# design.net
KiCad netlist of a schematic drawn in Altium Designer
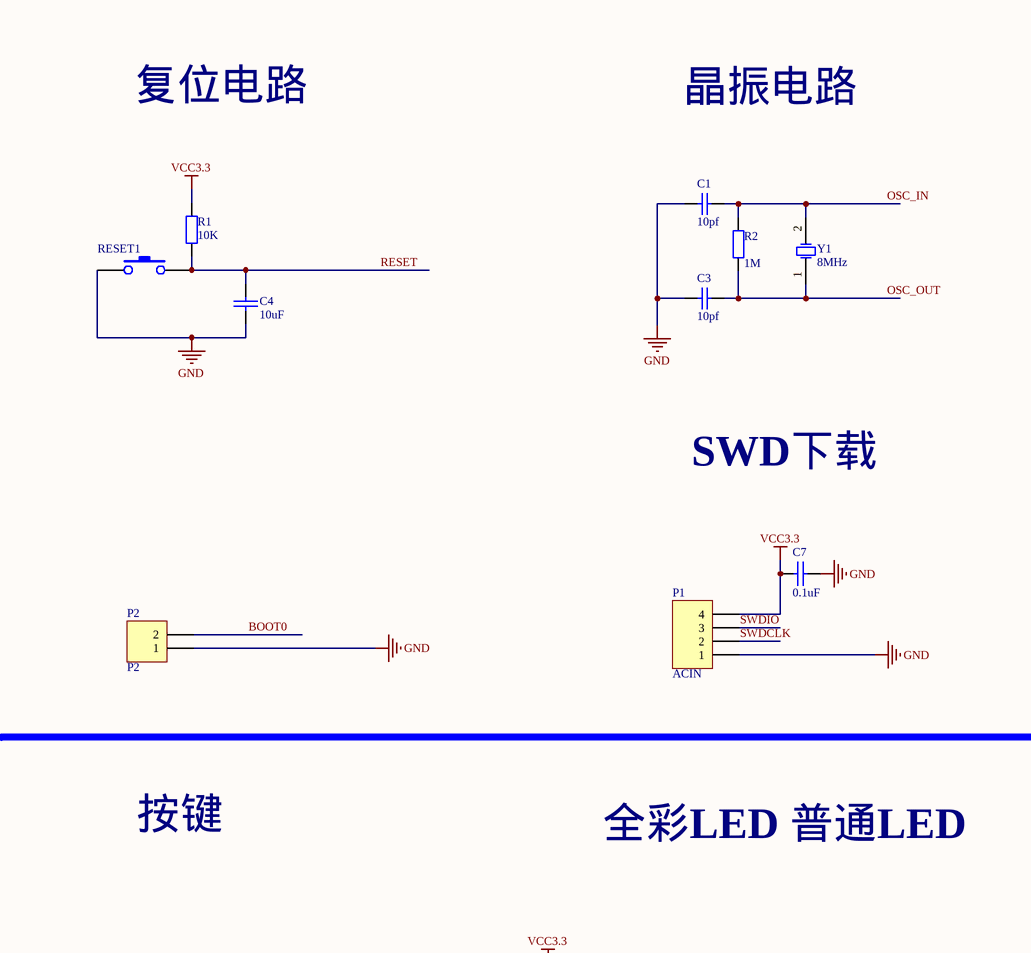
[diagram p0: 温湿度.SchDoc, top left]
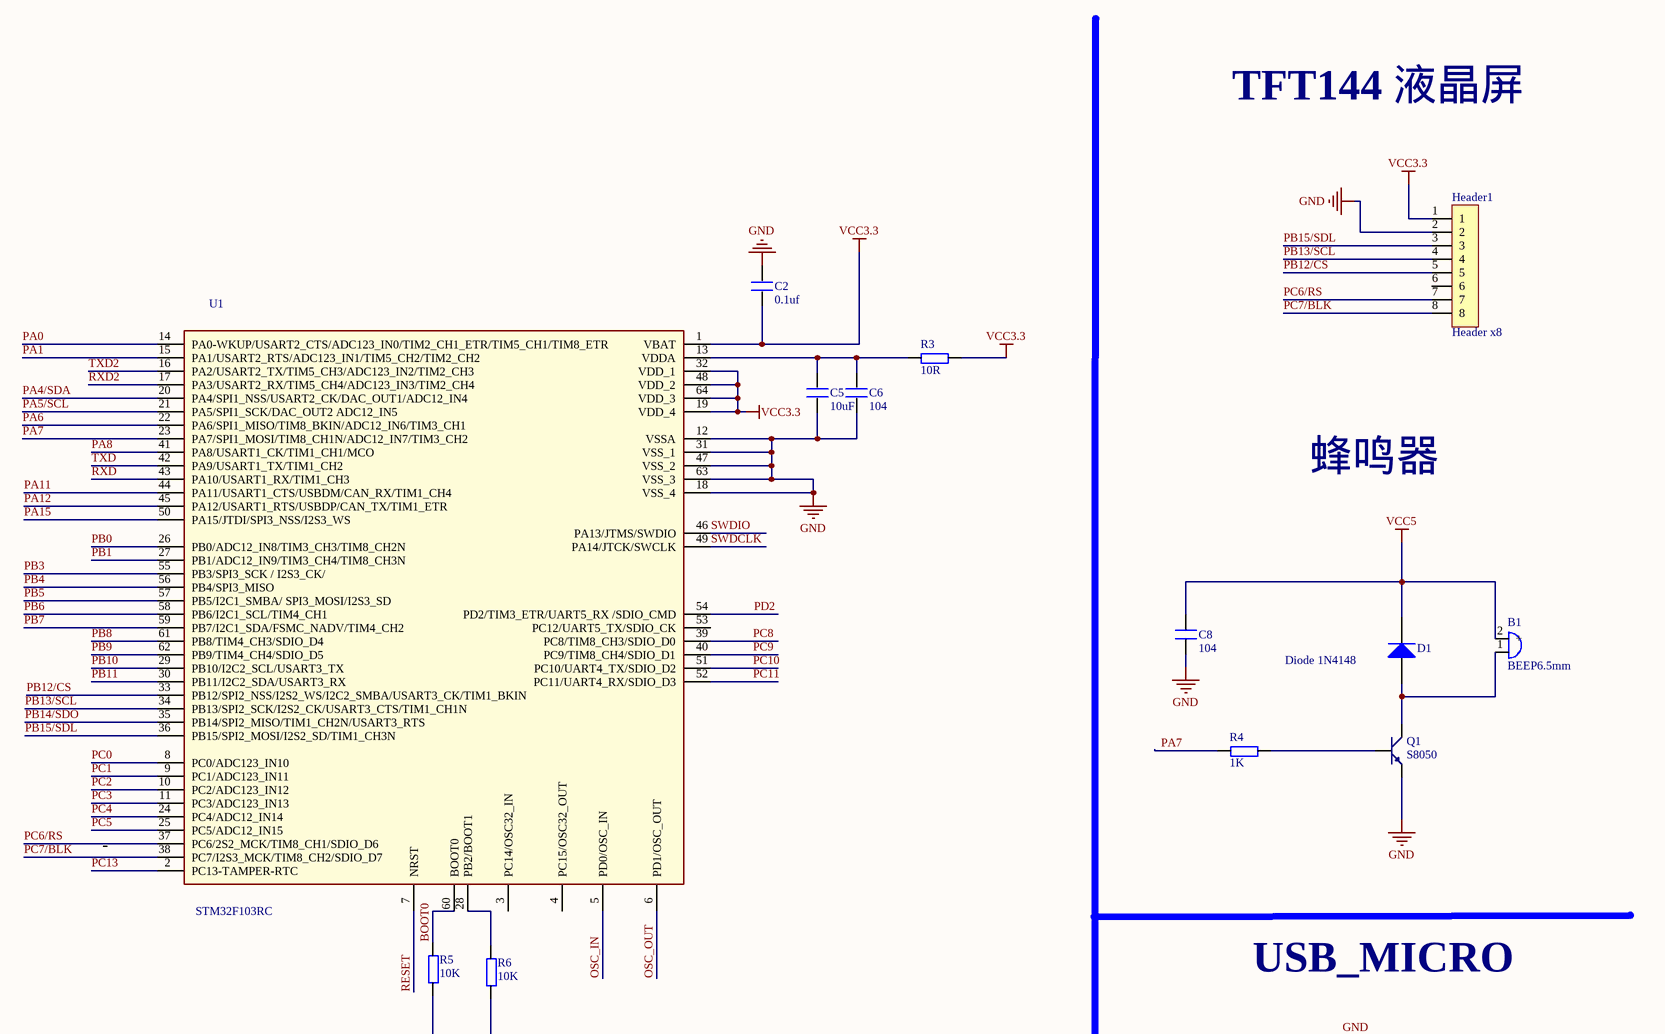
[diagram p1: 温湿度.SchDoc, top right]
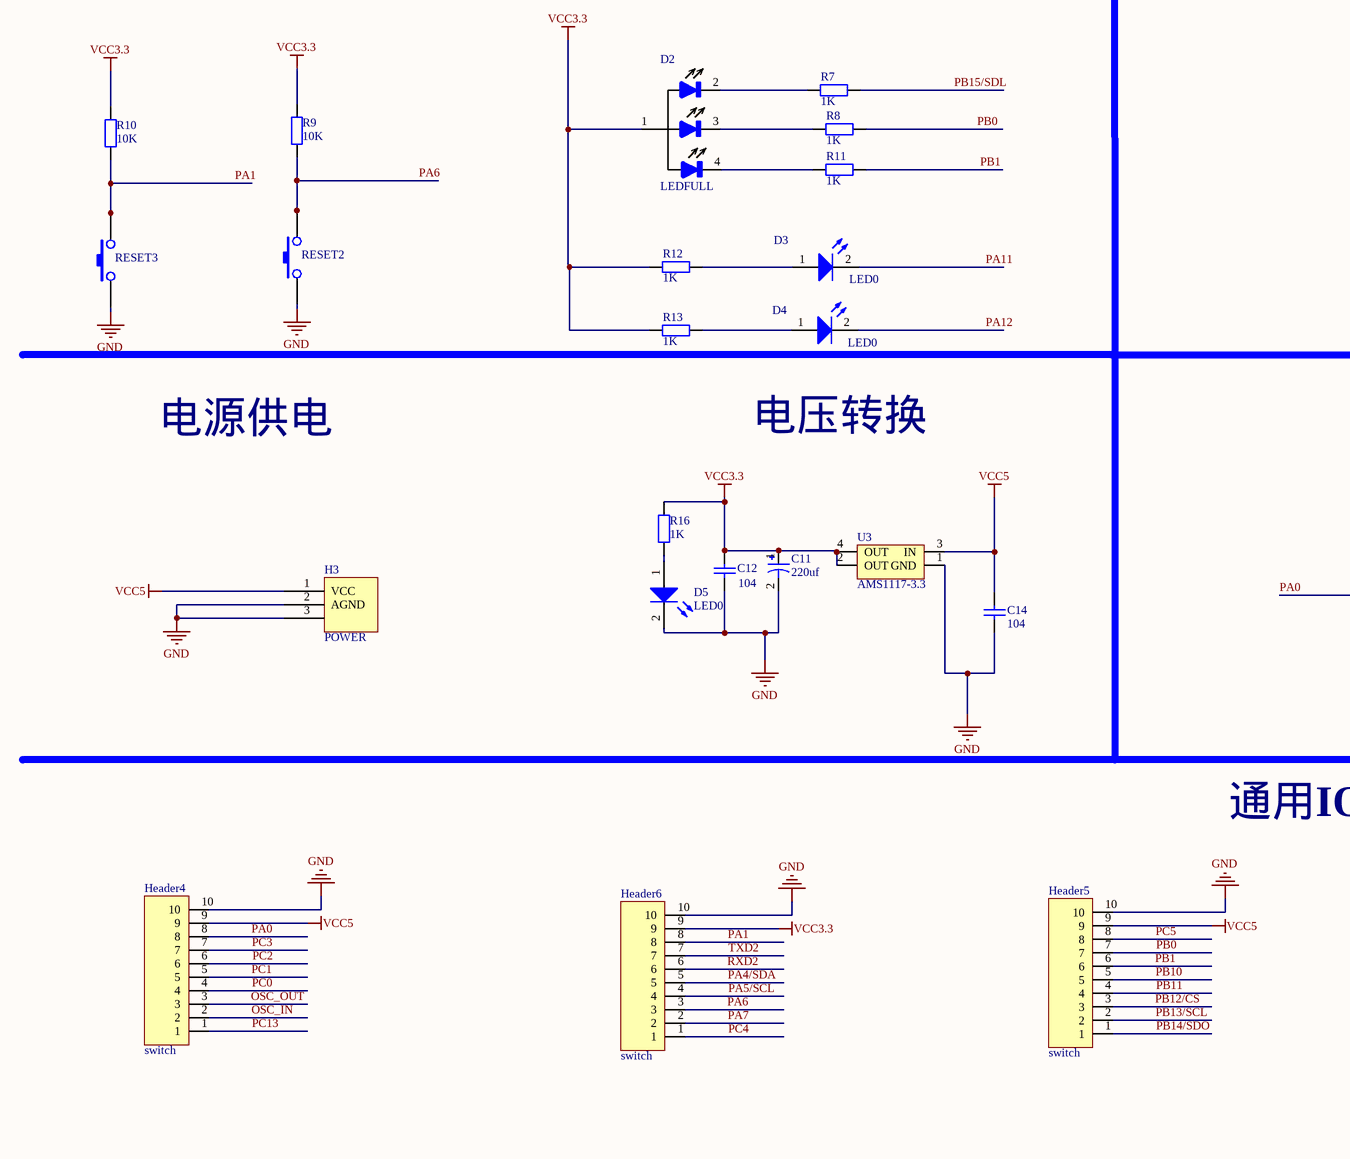
[diagram p2: 温湿度.SchDoc, bottom left]
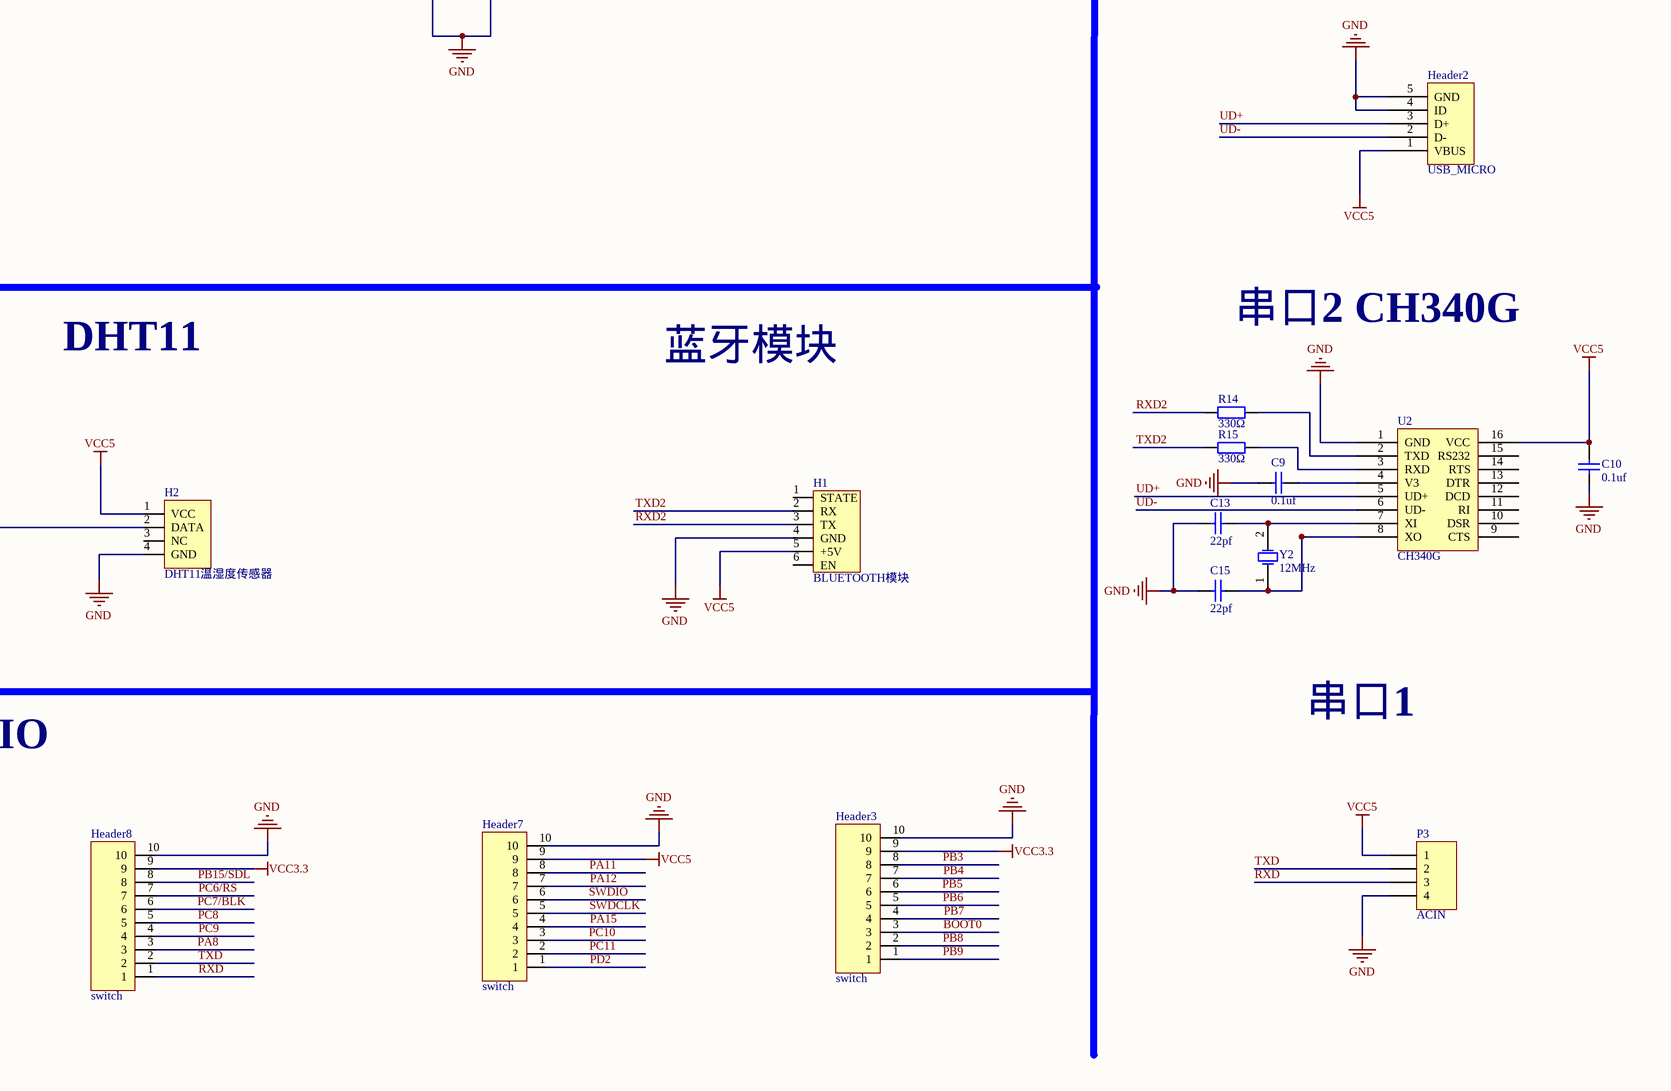
[diagram p3: 温湿度.SchDoc, bottom right]

(export (version "E")
  (design (tool "Eeschema 10.0.6"))
  (components
    (comp (ref "B1") (value "BEEP6.5mm") (footprint "BEEP 6.5x12x6") (libsource (lib "温湿度") (part "BEEP")))
    (comp (ref "C1")
      (value "10pf")
      (footprint "0805C")
      (description "Capacitor")
      (fields (field (name "PUBLISHER") "Altium Limited"))
      (libsource (lib "Miscellaneous Devices") (part "Cap"))
    )
    (comp (ref "C2") (value "0.1uf") (footprint "0805C") (libsource (lib "EliteSTM32封装库") (part "C")))
    (comp (ref "C3")
      (value "10pf")
      (footprint "0805C")
      (description "Capacitor")
      (fields (field (name "PUBLISHER") "Altium Limited"))
      (libsource (lib "Miscellaneous Devices") (part "Cap"))
    )
    (comp (ref "C4")
      (value "10uF")
      (footprint "0805C")
      (description "Capacitor")
      (libsource (lib "*") (part "CAP"))
    )
    (comp (ref "C5") (value "10uF") (footprint "0805C") (libsource (lib "EliteSTM32封装库") (part "C_2")))
    (comp (ref "C6") (value "104") (footprint "0805C") (libsource (lib "EliteSTM32封装库") (part "C")))
    (comp (ref "C7")
      (value "0.1uF")
      (footprint "0805C")
      (description "Capacitor")
      (libsource (lib "*") (part "CAP"))
    )
    (comp (ref "C8") (value "104") (footprint "0805C") (libsource (lib "EliteSTM32封装库") (part "C")))
    (comp (ref "C9")
      (value "0.1uf")
      (footprint "0805C")
      (description "Capacitor")
      (fields (field (name "PUBLISHER") "Altium Limited"))
      (libsource (lib "Miscellaneous Devices") (part "Cap"))
    )
    (comp (ref "C10")
      (value "0.1uf")
      (footprint "0805C")
      (description "Capacitor")
      (fields (field (name "PUBLISHER") "Altium Limited"))
      (libsource (lib "Miscellaneous Devices") (part "Cap"))
    )
    (comp (ref "C11")
      (value "220uf")
      (footprint "HDR2.54-LI-2P")
      (description "Polarized Capacitor (Surface Mount)")
      (fields (field (name "PUBLISHER") "Altium Limited"))
      (libsource (lib "Miscellaneous Devices") (part "Cap Pol3"))
    )
    (comp (ref "C12")
      (value "104")
      (footprint "0805C")
      (description "Capacitor")
      (fields (field (name "PUBLISHER") "Altium Limited"))
      (libsource (lib "Miscellaneous Devices") (part "Cap"))
    )
    (comp (ref "C13")
      (value "22pf")
      (footprint "0805C")
      (description "Capacitor")
      (fields (field (name "PUBLISHER") "Altium Limited"))
      (libsource (lib "Miscellaneous Devices") (part "Cap"))
    )
    (comp (ref "C14")
      (value "104")
      (footprint "0805C")
      (description "Capacitor")
      (fields (field (name "PUBLISHER") "Altium Limited"))
      (libsource (lib "Miscellaneous Devices") (part "Cap"))
    )
    (comp (ref "C15")
      (value "22pf")
      (footprint "0805C")
      (description "Capacitor")
      (fields (field (name "PUBLISHER") "Altium Limited"))
      (libsource (lib "Miscellaneous Devices") (part "Cap"))
    )
    (comp (ref "D1")
      (value "Diode 1N4148")
      (footprint "0805D")
      (description "High Conductance Fast Diode")
      (fields (field (name "PUBLISHER") "Altium Limited"))
      (libsource (lib "Miscellaneous Devices") (part "Diode 1N4148"))
    )
    (comp (ref "D2")
      (value "LEDFULL")
      (footprint "LEDFULL")
      (description "全彩LED")
      (libsource (lib "温湿度") (part "LEDFULL"))
    )
    (comp (ref "D3")
      (value "LED0")
      (footprint "LED_0805_B")
      (description "Typical INFRARED GaAs LED")
      (fields (field (name "PUBLISHER") "Altium Limited"))
      (libsource (lib "Miscellaneous Devices") (part "LED0"))
    )
    (comp (ref "D4")
      (value "LED0")
      (footprint "LED_0805_B")
      (description "Typical INFRARED GaAs LED")
      (fields (field (name "PUBLISHER") "Altium Limited"))
      (libsource (lib "Miscellaneous Devices") (part "LED0"))
    )
    (comp (ref "D5")
      (value "LED0")
      (footprint "LED_0805_B")
      (description "Typical INFRARED GaAs LED")
      (fields (field (name "PUBLISHER") "Altium Limited"))
      (libsource (lib "Miscellaneous Devices") (part "LED0"))
    )
    (comp (ref "H1") (value "BLUETOOTH模块") (footprint "BLUETOOTH") (libsource (lib "温湿度") (part "BLUETOOTH")))
    (comp (ref "H2") (value "DHT11温湿度传感器") (footprint "DHT11") (libsource (lib "温湿度") (part "DHT11")))
    (comp (ref "H3") (value "POWER") (footprint "DC-005") (libsource (lib "温湿度") (part "DC_IN")))
    (comp (ref "Header1")
      (value "Header x8")
      (footprint "HDR2.54-M-LI-8P")
      (description "红外2个 4VCC 4GND 2信号线")
      (libsource (lib "温湿度") (part "Header x8"))
    )
    (comp (ref "Header2")
      (value "USB_MICRO")
      (footprint "USB/SM0.8-6H5")
      (libsource (lib "温湿度") (part "USB_MICRO"))
    )
    (comp (ref "Header3")
      (value "switch")
      (footprint "HDR2.54-LI-10P")
      (libsource (lib "温湿度") (part "Header X10"))
    )
    (comp (ref "Header4")
      (value "switch")
      (footprint "HDR2.54-LI-10P")
      (libsource (lib "温湿度") (part "Header X10"))
    )
    (comp (ref "Header5")
      (value "switch")
      (footprint "HDR2.54-LI-10P")
      (libsource (lib "温湿度") (part "Header X10"))
    )
    (comp (ref "Header6")
      (value "switch")
      (footprint "HDR2.54-LI-10P")
      (libsource (lib "温湿度") (part "Header X10"))
    )
    (comp (ref "Header7")
      (value "switch")
      (footprint "HDR2.54-LI-10P")
      (libsource (lib "温湿度") (part "Header X10"))
    )
    (comp (ref "Header8")
      (value "switch")
      (footprint "HDR2.54-LI-10P")
      (libsource (lib "温湿度") (part "Header X10"))
    )
    (comp (ref "P1")
      (value "ACIN")
      (footprint "HDR2.54-LI-4P")
      (description "Header, 4-Pin")
      (fields (field (name "PUBLISHER") "Altium Limited"))
      (libsource (lib "") (part "P4_1"))
    )
    (comp (ref "P2")
      (value "P2")
      (footprint "HDR2.54-LI-2P")
      (description "Header, 2-Pin")
      (fields (field (name "PUBLISHER") "Altium Limited"))
      (libsource (lib "杨川的集成库") (part "P2"))
    )
    (comp (ref "P3")
      (value "ACIN")
      (footprint "HDR2.54-LI-4P")
      (description "Header, 4-Pin")
      (fields (field (name "PUBLISHER") "Altium Limited"))
      (libsource (lib "杨川的集成库") (part "P4"))
    )
    (comp (ref "Q1")
      (value "S8050")
      (footprint "SOT-23R")
      (description "8050/BCW846/BCW847")
      (libsource (lib "EliteSTM32封装库") (part "NPN"))
    )
    (comp (ref "R1")
      (value "10K")
      (footprint "0805R")
      (description "Resistor")
      (fields
        (field (name "MANUFACTURER") "Generic Components")
        (field (name "PUBLISHER") "Altium Hobart Technology Centre")
      )
      (libsource (lib "") (part "Res2_1"))
    )
    (comp (ref "R2")
      (value "1M")
      (footprint "0805R")
      (description "Resistor")
      (fields (field (name "Comment") "Res2") (field (name "PUBLISHER") "Altium Limited"))
      (libsource (lib "Miscellaneous Devices") (part "Res2"))
    )
    (comp (ref "R3") (value "10R") (footprint "0805R") (libsource (lib "EliteSTM32封装库") (part "R_1")))
    (comp (ref "R4") (value "1K") (footprint "0805R") (libsource (lib "EliteSTM32封装库") (part "R_1")))
    (comp (ref "R5") (value "10K") (footprint "0805R") (libsource (lib "EliteSTM32封装库") (part "R")))
    (comp (ref "R6") (value "10K") (footprint "0805R") (libsource (lib "EliteSTM32封装库") (part "R")))
    (comp (ref "R7")
      (value "1K")
      (footprint "0805R")
      (description "Resistor")
      (fields
        (field (name "MANUFACTURER") "Generic Components")
        (field (name "PUBLISHER") "Altium Hobart Technology Centre")
      )
      (libsource (lib "*") (part "Res2"))
    )
    (comp (ref "R8")
      (value "1K")
      (footprint "0805R")
      (description "Resistor")
      (fields
        (field (name "MANUFACTURER") "Generic Components")
        (field (name "PUBLISHER") "Altium Hobart Technology Centre")
      )
      (libsource (lib "*") (part "Res2"))
    )
    (comp (ref "R9")
      (value "10K")
      (footprint "0805R")
      (description "Resistor")
      (fields
        (field (name "MANUFACTURER") "Generic Components")
        (field (name "PUBLISHER") "Altium Hobart Technology Centre")
      )
      (libsource (lib "") (part "Res2_1"))
    )
    (comp (ref "R10")
      (value "10K")
      (footprint "0805R")
      (description "Resistor")
      (fields
        (field (name "MANUFACTURER") "Generic Components")
        (field (name "PUBLISHER") "Altium Hobart Technology Centre")
      )
      (libsource (lib "") (part "Res2_1"))
    )
    (comp (ref "R11")
      (value "1K")
      (footprint "0805R")
      (description "Resistor")
      (fields
        (field (name "MANUFACTURER") "Generic Components")
        (field (name "PUBLISHER") "Altium Hobart Technology Centre")
      )
      (libsource (lib "*") (part "Res2"))
    )
    (comp (ref "R12")
      (value "1K")
      (footprint "0805R")
      (description "Resistor")
      (fields
        (field (name "MANUFACTURER") "Generic Components")
        (field (name "PUBLISHER") "Altium Hobart Technology Centre")
      )
      (libsource (lib "*") (part "Res2"))
    )
    (comp (ref "R13")
      (value "1K")
      (footprint "0805R")
      (description "Resistor")
      (fields
        (field (name "MANUFACTURER") "Generic Components")
        (field (name "PUBLISHER") "Altium Hobart Technology Centre")
      )
      (libsource (lib "*") (part "Res2"))
    )
    (comp (ref "R14")
      (value "330Ω")
      (footprint "0805R")
      (description "Resistor")
      (fields
        (field (name "MANUFACTURER") "Generic Components")
        (field (name "PUBLISHER") "Altium Hobart Technology Centre")
      )
      (libsource (lib "*") (part "Res2"))
    )
    (comp (ref "R15")
      (value "330Ω")
      (footprint "0805R")
      (description "Resistor")
      (fields
        (field (name "MANUFACTURER") "Generic Components")
        (field (name "PUBLISHER") "Altium Hobart Technology Centre")
      )
      (libsource (lib "*") (part "Res2"))
    )
    (comp (ref "R16")
      (value "1K")
      (footprint "0805R")
      (description "Resistor")
      (fields
        (field (name "MANUFACTURER") "Generic Components")
        (field (name "PUBLISHER") "Altium Hobart Technology Centre")
      )
      (libsource (lib "") (part "Res2_1"))
    )
    (comp (ref "RESET1") (value "RESET") (footprint "QKEY") (libsource (lib "*") (part "SW-PB")))
    (comp (ref "RESET2") (value "RESET") (footprint "QKEY") (libsource (lib "*") (part "SW-PB")))
    (comp (ref "RESET3") (value "RESET") (footprint "QKEY") (libsource (lib "*") (part "SW-PB")))
    (comp (ref "U1")
      (value "STM32F103RC")
      (footprint "LQFP64-高密度")
      (libsource (lib "杨川的集成库") (part "STM32F103RC"))
    )
    (comp (ref "U2") (value "CH340G") (footprint "SOP16") (libsource (lib "温湿度") (part "CH340G")))
    (comp (ref "U3")
      (value "AMS1117-3.3")
      (footprint "AMS1117")
      (libsource (lib "Schlib1") (part "AMS1117-3.3"))
    )
    (comp (ref "Y1")
      (value "8MHz")
      (footprint "OSC HC-49SMD")
      (description "Crystal Oscillator")
      (fields (field (name "PUBLISHER") "Altium Limited"))
      (libsource (lib "EliteSTM32封装库") (part "XTAL"))
    )
    (comp (ref "Y2")
      (value "12MHz")
      (footprint "OSC HC-49SMD")
      (description "Crystal Oscillator")
      (fields (field (name "PUBLISHER") "Altium Limited"))
      (libsource (lib "EliteSTM32封装库") (part "XTAL"))
    )
  )
  (nets
    (net (code "2") (name "/BOOT0") (class "Default")
      (node (ref "Header3") (pin "3") (pinfunction "3_3") (pintype "passive"))
      (node (ref "P2") (pin "2") (pinfunction "2_2") (pintype "passive"))
      (node (ref "R5") (pin "2") (pintype "passive"))
      (node (ref "U1") (pin "60") (pinfunction "BOOT0_60") (pintype "passive"))
    )
    (net (code "3") (name "/OSC_IN") (class "Default")
      (node (ref "C1") (pin "2") (pinfunction "2_2") (pintype "passive"))
      (node (ref "Header4") (pin "2") (pinfunction "2_2") (pintype "passive"))
      (node (ref "R2") (pin "2") (pinfunction "2_2") (pintype "passive"))
      (node (ref "U1") (pin "5") (pinfunction "PD0/OSC_IN_5") (pintype "passive"))
      (node (ref "Y1") (pin "2") (pinfunction "OSC2_2") (pintype "passive"))
    )
    (net (code "4") (name "/OSC_OUT") (class "Default")
      (node (ref "C3") (pin "2") (pinfunction "2_2") (pintype "passive"))
      (node (ref "Header4") (pin "3") (pinfunction "3_3") (pintype "passive"))
      (node (ref "R2") (pin "1") (pinfunction "1_1") (pintype "passive"))
      (node (ref "U1") (pin "6") (pinfunction "PD1/OSC_OUT_6") (pintype "passive"))
      (node (ref "Y1") (pin "1") (pinfunction "OSC1_1") (pintype "passive"))
    )
    (net (code "5") (name "/PA0") (class "Default")
      (node (ref "H2") (pin "2") (pinfunction "DATA_2") (pintype "passive"))
      (node (ref "Header4") (pin "8") (pinfunction "8_8") (pintype "passive"))
      (node (ref "U1") (pin "14") (pinfunction "PA0-WKUP/USART2_CTS/ADC123_IN0/TIM2_CH1_ETR/TIM5_CH1/TIM8_ETR_14") (pintype "passive"))
    )
    (net (code "6") (name "/PA1") (class "Default")
      (node (ref "Header6") (pin "8") (pinfunction "8_8") (pintype "passive"))
      (node (ref "R10") (pin "2") (pinfunction "2_2") (pintype "passive"))
      (node (ref "RESET3") (pin "2") (pinfunction "2_2") (pintype "passive"))
      (node (ref "U1") (pin "15") (pinfunction "PA1/USART2_RTS/ADC123_IN1/TIM5_CH2/TIM2_CH2_15") (pintype "passive"))
    )
    (net (code "7") (name "/PA4{slash}SDA") (class "Default")
      (node (ref "Header6") (pin "5") (pinfunction "5_5") (pintype "passive"))
      (node (ref "U1") (pin "20") (pinfunction "PA4/SPI1_NSS/USART2_CK/DAC_OUT1/ADC12_IN4_20") (pintype "passive"))
    )
    (net (code "8") (name "/PA5{slash}SCL") (class "Default")
      (node (ref "Header6") (pin "4") (pinfunction "4_4") (pintype "passive"))
      (node (ref "U1") (pin "21") (pinfunction "PA5/SPI1_SCK/DAC_OUT2_ADC12_IN5_21") (pintype "passive"))
    )
    (net (code "9") (name "/PA6") (class "Default")
      (node (ref "Header6") (pin "3") (pinfunction "3_3") (pintype "passive"))
      (node (ref "R9") (pin "2") (pinfunction "2_2") (pintype "passive"))
      (node (ref "RESET2") (pin "2") (pinfunction "2_2") (pintype "passive"))
      (node (ref "U1") (pin "22") (pinfunction "PA6/SPI1_MISO/TIM8_BKIN/ADC12_IN6/TIM3_CH1_22") (pintype "passive"))
    )
    (net (code "10") (name "/PA7") (class "Default")
      (node (ref "Header6") (pin "2") (pinfunction "2_2") (pintype "passive"))
      (node (ref "R4") (pin "1") (pintype "passive"))
      (node (ref "U1") (pin "23") (pinfunction "PA7/SPI1_MOSI/TIM8_CH1N/ADC12_IN7/TIM3_CH2_23") (pintype "passive"))
    )
    (net (code "11") (name "/PA8") (class "Default")
      (node (ref "Header8") (pin "3") (pinfunction "3_3") (pintype "passive"))
      (node (ref "U1") (pin "41") (pinfunction "PA8/USART1_CK/TIM1_CH1/MCO_41") (pintype "passive"))
    )
    (net (code "12") (name "/PA11") (class "Default")
      (node (ref "D3") (pin "2") (pinfunction "K_2") (pintype "passive"))
      (node (ref "Header7") (pin "8") (pinfunction "8_8") (pintype "passive"))
      (node (ref "U1") (pin "44") (pinfunction "PA11/USART1_CTS/USBDM/CAN_RX/TIM1_CH4_44") (pintype "passive"))
    )
    (net (code "13") (name "/PA12") (class "Default")
      (node (ref "D4") (pin "2") (pinfunction "K_2") (pintype "passive"))
      (node (ref "Header7") (pin "7") (pinfunction "7_7") (pintype "passive"))
      (node (ref "U1") (pin "45") (pinfunction "PA12/USART1_RTS/USBDP/CAN_TX/TIM1_ETR_45") (pintype "passive"))
    )
    (net (code "14") (name "/PA15") (class "Default")
      (node (ref "Header7") (pin "4") (pinfunction "4_4") (pintype "passive"))
      (node (ref "U1") (pin "50") (pinfunction "PA15/JTDI/SPI3_NSS/I2S3_WS_50") (pintype "passive"))
    )
    (net (code "15") (name "/PB0") (class "Default")
      (node (ref "Header5") (pin "7") (pinfunction "7_7") (pintype "passive"))
      (node (ref "R8") (pin "2") (pinfunction "2_2") (pintype "passive"))
      (node (ref "U1") (pin "26") (pinfunction "PB0/ADC12_IN8/TIM3_CH3/TIM8_CH2N_26") (pintype "passive"))
    )
    (net (code "16") (name "/PB1") (class "Default")
      (node (ref "Header5") (pin "6") (pinfunction "6_6") (pintype "passive"))
      (node (ref "R11") (pin "2") (pinfunction "2_2") (pintype "passive"))
      (node (ref "U1") (pin "27") (pinfunction "PB1/ADC12_IN9/TIM3_CH4/TIM8_CH3N_27") (pintype "passive"))
    )
    (net (code "17") (name "/PB3") (class "Default")
      (node (ref "Header3") (pin "8") (pinfunction "8_8") (pintype "passive"))
      (node (ref "U1") (pin "55") (pinfunction "PB3/SPI3_SCK_/_I2S3_CK/_55") (pintype "passive"))
    )
    (net (code "18") (name "/PB4") (class "Default")
      (node (ref "Header3") (pin "7") (pinfunction "7_7") (pintype "passive"))
      (node (ref "U1") (pin "56") (pinfunction "PB4/SPI3_MISO_56") (pintype "passive"))
    )
    (net (code "19") (name "/PB5") (class "Default")
      (node (ref "Header3") (pin "6") (pinfunction "6_6") (pintype "passive"))
      (node (ref "U1") (pin "57") (pinfunction "PB5/I2C1_SMBA/_SPI3_MOSI/I2S3_SD_57") (pintype "passive"))
    )
    (net (code "20") (name "/PB6") (class "Default")
      (node (ref "Header3") (pin "5") (pinfunction "5_5") (pintype "passive"))
      (node (ref "U1") (pin "58") (pinfunction "PB6/I2C1_SCL/TIM4_CH1_58") (pintype "passive"))
    )
    (net (code "21") (name "/PB7") (class "Default")
      (node (ref "Header3") (pin "4") (pinfunction "4_4") (pintype "passive"))
      (node (ref "U1") (pin "59") (pinfunction "PB7/I2C1_SDA/FSMC_NADV/TIM4_CH2_59") (pintype "passive"))
    )
    (net (code "22") (name "/PB8") (class "Default")
      (node (ref "Header3") (pin "2") (pinfunction "2_2") (pintype "passive"))
      (node (ref "U1") (pin "61") (pinfunction "PB8/TIM4_CH3/SDIO_D4_61") (pintype "passive"))
    )
    (net (code "23") (name "/PB9") (class "Default")
      (node (ref "Header3") (pin "1") (pinfunction "1_1") (pintype "passive"))
      (node (ref "U1") (pin "62") (pinfunction "PB9/TIM4_CH4/SDIO_D5_62") (pintype "passive"))
    )
    (net (code "24") (name "/PB10") (class "Default")
      (node (ref "Header5") (pin "5") (pinfunction "5_5") (pintype "passive"))
      (node (ref "U1") (pin "29") (pinfunction "PB10/I2C2_SCL/USART3_TX_29") (pintype "passive"))
    )
    (net (code "25") (name "/PB11") (class "Default")
      (node (ref "Header5") (pin "4") (pinfunction "4_4") (pintype "passive"))
      (node (ref "U1") (pin "30") (pinfunction "PB11/I2C2_SDA/USART3_RX_30") (pintype "passive"))
    )
    (net (code "26") (name "/PB12{slash}CS") (class "Default")
      (node (ref "Header1") (pin "5") (pinfunction "5_5") (pintype "passive"))
      (node (ref "Header5") (pin "3") (pinfunction "3_3") (pintype "passive"))
      (node (ref "U1") (pin "33") (pinfunction "PB12/SPI2_NSS/I2S2_WS/I2C2_SMBA/USART3_CK/TIM1_BKIN_33") (pintype "passive"))
    )
    (net (code "27") (name "/PB13{slash}SCL") (class "Default")
      (node (ref "Header1") (pin "4") (pinfunction "4_4") (pintype "passive"))
      (node (ref "Header5") (pin "2") (pinfunction "2_2") (pintype "passive"))
      (node (ref "U1") (pin "34") (pinfunction "PB13/SPI2_SCK/I2S2_CK/USART3_CTS/TIM1_CH1N_34") (pintype "passive"))
    )
    (net (code "28") (name "/PB14{slash}SDO") (class "Default")
      (node (ref "Header5") (pin "1") (pinfunction "1_1") (pintype "passive"))
      (node (ref "U1") (pin "35") (pinfunction "PB14/SPI2_MISO/TIM1_CH2N/USART3_RTS_35") (pintype "passive"))
    )
    (net (code "29") (name "/PB15{slash}SDL") (class "Default")
      (node (ref "Header1") (pin "3") (pinfunction "3_3") (pintype "passive"))
      (node (ref "Header8") (pin "8") (pinfunction "8_8") (pintype "passive"))
      (node (ref "R7") (pin "2") (pinfunction "2_2") (pintype "passive"))
      (node (ref "U1") (pin "36") (pinfunction "PB15/SPI2_MOSI/I2S2_SD/TIM1_CH3N_36") (pintype "passive"))
    )
    (net (code "30") (name "/PC0") (class "Default")
      (node (ref "Header4") (pin "4") (pinfunction "4_4") (pintype "passive"))
      (node (ref "U1") (pin "8") (pinfunction "PC0/ADC123_IN10_8") (pintype "passive"))
    )
    (net (code "31") (name "/PC1") (class "Default")
      (node (ref "Header4") (pin "5") (pinfunction "5_5") (pintype "passive"))
      (node (ref "U1") (pin "9") (pinfunction "PC1/ADC123_IN11_9") (pintype "passive"))
    )
    (net (code "32") (name "/PC2") (class "Default")
      (node (ref "Header4") (pin "6") (pinfunction "6_6") (pintype "passive"))
      (node (ref "U1") (pin "10") (pinfunction "PC2/ADC123_IN12_10") (pintype "passive"))
    )
    (net (code "33") (name "/PC3") (class "Default")
      (node (ref "Header4") (pin "7") (pinfunction "7_7") (pintype "passive"))
      (node (ref "U1") (pin "11") (pinfunction "PC3/ADC123_IN13_11") (pintype "passive"))
    )
    (net (code "34") (name "/PC4") (class "Default")
      (node (ref "Header6") (pin "1") (pinfunction "1_1") (pintype "passive"))
      (node (ref "U1") (pin "24") (pinfunction "PC4/ADC12_IN14_24") (pintype "passive"))
    )
    (net (code "35") (name "/PC5") (class "Default")
      (node (ref "Header5") (pin "8") (pinfunction "8_8") (pintype "passive"))
      (node (ref "U1") (pin "25") (pinfunction "PC5/ADC12_IN15_25") (pintype "passive"))
    )
    (net (code "36") (name "/PC6{slash}RS") (class "Default")
      (node (ref "Header1") (pin "7") (pinfunction "7_7") (pintype "passive"))
      (node (ref "Header8") (pin "7") (pinfunction "7_7") (pintype "passive"))
      (node (ref "U1") (pin "37") (pinfunction "PC6/2S2_MCK/TIM8_CH1/SDIO_D6_37") (pintype "passive"))
    )
    (net (code "37") (name "/PC7{slash}BLK") (class "Default")
      (node (ref "Header1") (pin "8") (pinfunction "8_8") (pintype "passive"))
      (node (ref "Header8") (pin "6") (pinfunction "6_6") (pintype "passive"))
      (node (ref "U1") (pin "38") (pinfunction "PC7/I2S3_MCK/TIM8_CH2/SDIO_D7_38") (pintype "passive"))
    )
    (net (code "38") (name "/PC8") (class "Default")
      (node (ref "Header8") (pin "5") (pinfunction "5_5") (pintype "passive"))
      (node (ref "U1") (pin "39") (pinfunction "PC8/TIM8_CH3/SDIO_D0_39") (pintype "passive"))
    )
    (net (code "39") (name "/PC9") (class "Default")
      (node (ref "Header8") (pin "4") (pinfunction "4_4") (pintype "passive"))
      (node (ref "U1") (pin "40") (pinfunction "PC9/TIM8_CH4/SDIO_D1_40") (pintype "passive"))
    )
    (net (code "40") (name "/PC10") (class "Default")
      (node (ref "Header7") (pin "3") (pinfunction "3_3") (pintype "passive"))
      (node (ref "U1") (pin "51") (pinfunction "PC10/UART4_TX/SDIO_D2_51") (pintype "passive"))
    )
    (net (code "41") (name "/PC11") (class "Default")
      (node (ref "Header7") (pin "2") (pinfunction "2_2") (pintype "passive"))
      (node (ref "U1") (pin "52") (pinfunction "PC11/UART4_RX/SDIO_D3_52") (pintype "passive"))
    )
    (net (code "42") (name "/PC13") (class "Default")
      (node (ref "Header4") (pin "1") (pinfunction "1_1") (pintype "passive"))
      (node (ref "U1") (pin "2") (pinfunction "PC13-TAMPER-RTC_2") (pintype "passive"))
    )
    (net (code "43") (name "/PD2") (class "Default")
      (node (ref "Header7") (pin "1") (pinfunction "1_1") (pintype "passive"))
      (node (ref "U1") (pin "54") (pinfunction "PD2/TIM3_ETR/UART5_RX_/SDIO_CMD_54") (pintype "passive"))
    )
    (net (code "44") (name "/RESET") (class "Default")
      (node (ref "C4") (pin "1") (pinfunction "1_1") (pintype "passive"))
      (node (ref "R1") (pin "2") (pinfunction "2_2") (pintype "passive"))
      (node (ref "RESET1") (pin "2") (pinfunction "2_2") (pintype "passive"))
      (node (ref "U1") (pin "7") (pinfunction "NRST_7") (pintype "passive"))
    )
    (net (code "45") (name "/RXD") (class "Default")
      (node (ref "Header8") (pin "1") (pinfunction "1_1") (pintype "passive"))
      (node (ref "P3") (pin "3") (pinfunction "3_3") (pintype "passive"))
      (node (ref "U1") (pin "43") (pinfunction "PA10/USART1_RX/TIM1_CH3_43") (pintype "passive"))
    )
    (net (code "46") (name "/RXD2") (class "Default")
      (node (ref "H1") (pin "3") (pinfunction "TX_3") (pintype "passive"))
      (node (ref "Header6") (pin "6") (pinfunction "6_6") (pintype "passive"))
      (node (ref "R14") (pin "1") (pinfunction "1_1") (pintype "passive"))
      (node (ref "U1") (pin "17") (pinfunction "PA3/USART2_RX/TIM5_CH4/ADC123_IN3/TIM2_CH4_17") (pintype "passive"))
    )
    (net (code "47") (name "/SWDCLK") (class "Default")
      (node (ref "Header7") (pin "5") (pinfunction "5_5") (pintype "passive"))
      (node (ref "P1") (pin "2") (pinfunction "2_2") (pintype "passive"))
      (node (ref "U1") (pin "49") (pinfunction "PA14/JTCK/SWCLK_49") (pintype "passive"))
    )
    (net (code "48") (name "/SWDIO") (class "Default")
      (node (ref "Header7") (pin "6") (pinfunction "6_6") (pintype "passive"))
      (node (ref "P1") (pin "3") (pinfunction "3_3") (pintype "passive"))
      (node (ref "U1") (pin "46") (pinfunction "PA13/JTMS/SWDIO_46") (pintype "passive"))
    )
    (net (code "49") (name "/TXD") (class "Default")
      (node (ref "Header8") (pin "2") (pinfunction "2_2") (pintype "passive"))
      (node (ref "P3") (pin "2") (pinfunction "2_2") (pintype "passive"))
      (node (ref "U1") (pin "42") (pinfunction "PA9/USART1_TX/TIM1_CH2_42") (pintype "passive"))
    )
    (net (code "50") (name "/TXD2") (class "Default")
      (node (ref "H1") (pin "2") (pinfunction "RX_2") (pintype "passive"))
      (node (ref "Header6") (pin "7") (pinfunction "7_7") (pintype "passive"))
      (node (ref "R15") (pin "1") (pinfunction "1_1") (pintype "passive"))
      (node (ref "U1") (pin "16") (pinfunction "PA2/USART2_TX/TIM5_CH3/ADC123_IN2/TIM2_CH3_16") (pintype "passive"))
    )
    (net (code "51") (name "/UD+") (class "Default")
      (node (ref "Header2") (pin "3") (pinfunction "D+_3") (pintype "passive"))
      (node (ref "U2") (pin "5") (pinfunction "UD+_5") (pintype "passive"))
    )
    (net (code "52") (name "/UD-") (class "Default")
      (node (ref "Header2") (pin "2") (pinfunction "D-_2") (pintype "passive"))
      (node (ref "U2") (pin "6") (pinfunction "UD-_6") (pintype "passive"))
    )
    (net (code "53") (name "GND") (class "Default")
      (node (ref "C1") (pin "1") (pinfunction "1_1") (pintype "passive"))
      (node (ref "C10") (pin "1") (pinfunction "1_1") (pintype "passive"))
      (node (ref "C11") (pin "2") (pinfunction "2_2") (pintype "passive"))
      (node (ref "C12") (pin "1") (pinfunction "1_1") (pintype "passive"))
      (node (ref "C13") (pin "2") (pinfunction "2_2") (pintype "passive"))
      (node (ref "C14") (pin "1") (pinfunction "1_1") (pintype "passive"))
      (node (ref "C15") (pin "2") (pinfunction "2_2") (pintype "passive"))
      (node (ref "C2") (pin "2") (pintype "passive"))
      (node (ref "C3") (pin "1") (pinfunction "1_1") (pintype "passive"))
      (node (ref "C4") (pin "2") (pinfunction "2_2") (pintype "passive"))
      (node (ref "C5") (pin "1") (pintype "passive"))
      (node (ref "C6") (pin "1") (pintype "passive"))
      (node (ref "C7") (pin "2") (pinfunction "2_2") (pintype "passive"))
      (node (ref "C8") (pin "1") (pintype "passive"))
      (node (ref "C9") (pin "2") (pinfunction "2_2") (pintype "passive"))
      (node (ref "D5") (pin "2") (pinfunction "K_2") (pintype "passive"))
      (node (ref "H1") (pin "4") (pinfunction "GND_4") (pintype "passive"))
      (node (ref "H2") (pin "4") (pinfunction "GND_4") (pintype "passive"))
      (node (ref "H3") (pin "2") (pinfunction "AGND_2") (pintype "passive"))
      (node (ref "H3") (pin "3") (pintype "passive"))
      (node (ref "Header1") (pin "2") (pinfunction "2_2") (pintype "passive"))
      (node (ref "Header2") (pin "4") (pinfunction "ID_4") (pintype "passive"))
      (node (ref "Header2") (pin "5") (pinfunction "GND_5") (pintype "passive"))
      (node (ref "Header3") (pin "10") (pinfunction "10_10") (pintype "passive"))
      (node (ref "Header4") (pin "10") (pinfunction "10_10") (pintype "passive"))
      (node (ref "Header5") (pin "10") (pinfunction "10_10") (pintype "passive"))
      (node (ref "Header6") (pin "10") (pinfunction "10_10") (pintype "passive"))
      (node (ref "Header7") (pin "10") (pinfunction "10_10") (pintype "passive"))
      (node (ref "Header8") (pin "10") (pinfunction "10_10") (pintype "passive"))
      (node (ref "P1") (pin "1") (pinfunction "1_1") (pintype "passive"))
      (node (ref "P2") (pin "1") (pinfunction "1_1") (pintype "passive"))
      (node (ref "P3") (pin "4") (pinfunction "4_4") (pintype "passive"))
      (node (ref "Q1") (pin "1") (pinfunction "E_1") (pintype "passive"))
      (node (ref "R5") (pin "1") (pintype "passive"))
      (node (ref "R6") (pin "1") (pintype "passive"))
      (node (ref "RESET1") (pin "1") (pinfunction "1_1") (pintype "passive"))
      (node (ref "RESET2") (pin "1") (pinfunction "1_1") (pintype "passive"))
      (node (ref "RESET3") (pin "1") (pinfunction "1_1") (pintype "passive"))
      (node (ref "U1") (pin "12") (pinfunction "VSSA_12") (pintype "passive"))
      (node (ref "U1") (pin "18") (pinfunction "VSS_4_18") (pintype "passive"))
      (node (ref "U1") (pin "31") (pinfunction "VSS_1_31") (pintype "passive"))
      (node (ref "U1") (pin "47") (pinfunction "VSS_2_47") (pintype "passive"))
      (node (ref "U1") (pin "63") (pinfunction "VSS_3_63") (pintype "passive"))
      (node (ref "U2") (pin "1") (pinfunction "GND_1") (pintype "passive"))
      (node (ref "U3") (pin "1") (pinfunction "GND_1") (pintype "passive"))
    )
    (net (code "54") (name "Net-(D1-A)") (class "Default")
      (node (ref "B1") (pin "1") (pintype "passive"))
      (node (ref "D1") (pin "1") (pinfunction "A_1") (pintype "passive"))
      (node (ref "Q1") (pin "3") (pinfunction "C_3") (pintype "passive"))
    )
    (net (code "55") (name "Net-(D2-Pad2)") (class "Default")
      (node (ref "D2") (pin "2") (pinfunction "2_2") (pintype "passive"))
      (node (ref "R7") (pin "1") (pinfunction "1_1") (pintype "passive"))
    )
    (net (code "56") (name "Net-(D2-Pad3)") (class "Default")
      (node (ref "D2") (pin "3") (pinfunction "3_3") (pintype "passive"))
      (node (ref "R8") (pin "1") (pinfunction "1_1") (pintype "passive"))
    )
    (net (code "57") (name "Net-(D2-Pad4)") (class "Default")
      (node (ref "D2") (pin "4") (pinfunction "4_4") (pintype "passive"))
      (node (ref "R11") (pin "1") (pinfunction "1_1") (pintype "passive"))
    )
    (net (code "58") (name "Net-(D3-A)") (class "Default")
      (node (ref "D3") (pin "1") (pinfunction "A_1") (pintype "passive"))
      (node (ref "R12") (pin "2") (pinfunction "2_2") (pintype "passive"))
    )
    (net (code "59") (name "Net-(D4-A)") (class "Default")
      (node (ref "D4") (pin "1") (pinfunction "A_1") (pintype "passive"))
      (node (ref "R13") (pin "2") (pinfunction "2_2") (pintype "passive"))
    )
    (net (code "60") (name "Net-(D5-A)") (class "Default")
      (node (ref "D5") (pin "1") (pinfunction "A_1") (pintype "passive"))
      (node (ref "R16") (pin "2") (pinfunction "2_2") (pintype "passive"))
    )
    (net (code "61") (name "Net-(Q1-B)") (class "Default")
      (node (ref "Q1") (pin "2") (pinfunction "B_2") (pintype "passive"))
      (node (ref "R4") (pin "2") (pintype "passive"))
    )
    (net (code "62") (name "Net-(U1-PB2{slash}BOOT1)") (class "Default")
      (node (ref "R6") (pin "2") (pintype "passive"))
      (node (ref "U1") (pin "28") (pinfunction "PB2/BOOT1_28") (pintype "passive"))
    )
    (net (code "63") (name "Net-(U1-VDDA)") (class "Default")
      (node (ref "C5") (pin "2") (pintype "passive"))
      (node (ref "C6") (pin "2") (pintype "passive"))
      (node (ref "R3") (pin "1") (pintype "passive"))
      (node (ref "U1") (pin "13") (pinfunction "VDDA_13") (pintype "passive"))
    )
    (net (code "64") (name "Net-(U2-RXD)") (class "Default")
      (node (ref "R15") (pin "2") (pinfunction "2_2") (pintype "passive"))
      (node (ref "U2") (pin "3") (pinfunction "RXD_3") (pintype "passive"))
    )
    (net (code "65") (name "Net-(U2-TXD)") (class "Default")
      (node (ref "R14") (pin "2") (pinfunction "2_2") (pintype "passive"))
      (node (ref "U2") (pin "2") (pinfunction "TXD_2") (pintype "passive"))
    )
    (net (code "66") (name "Net-(U2-V3)") (class "Default")
      (node (ref "C9") (pin "1") (pinfunction "1_1") (pintype "passive"))
      (node (ref "U2") (pin "4") (pinfunction "V3_4") (pintype "passive"))
    )
    (net (code "67") (name "Net-(U2-XI)") (class "Default")
      (node (ref "C13") (pin "1") (pinfunction "1_1") (pintype "passive"))
      (node (ref "U2") (pin "7") (pinfunction "XI_7") (pintype "passive"))
      (node (ref "Y2") (pin "2") (pinfunction "OSC2_2") (pintype "passive"))
    )
    (net (code "68") (name "Net-(U2-XO)") (class "Default")
      (node (ref "C15") (pin "1") (pinfunction "1_1") (pintype "passive"))
      (node (ref "U2") (pin "8") (pinfunction "XO_8") (pintype "passive"))
      (node (ref "Y2") (pin "1") (pinfunction "OSC1_1") (pintype "passive"))
    )
    (net (code "69") (name "VCC3.3") (class "Default")
      (node (ref "C11") (pin "1") (pinfunction "1_1") (pintype "passive"))
      (node (ref "C12") (pin "2") (pinfunction "2_2") (pintype "passive"))
      (node (ref "C2") (pin "1") (pintype "passive"))
      (node (ref "C7") (pin "1") (pinfunction "1_1") (pintype "passive"))
      (node (ref "D2") (pin "1") (pinfunction "1_1") (pintype "passive"))
      (node (ref "Header1") (pin "1") (pinfunction "1_1") (pintype "passive"))
      (node (ref "Header3") (pin "9") (pinfunction "9_9") (pintype "passive"))
      (node (ref "Header6") (pin "9") (pinfunction "9_9") (pintype "passive"))
      (node (ref "Header8") (pin "9") (pinfunction "9_9") (pintype "passive"))
      (node (ref "P1") (pin "4") (pinfunction "4_4") (pintype "passive"))
      (node (ref "R1") (pin "1") (pinfunction "1_1") (pintype "passive"))
      (node (ref "R10") (pin "1") (pinfunction "1_1") (pintype "passive"))
      (node (ref "R12") (pin "1") (pinfunction "1_1") (pintype "passive"))
      (node (ref "R13") (pin "1") (pinfunction "1_1") (pintype "passive"))
      (node (ref "R16") (pin "1") (pinfunction "1_1") (pintype "passive"))
      (node (ref "R3") (pin "2") (pintype "passive"))
      (node (ref "R9") (pin "1") (pinfunction "1_1") (pintype "passive"))
      (node (ref "U1") (pin "1") (pinfunction "VBAT_1") (pintype "passive"))
      (node (ref "U1") (pin "19") (pinfunction "VDD_4_19") (pintype "passive"))
      (node (ref "U1") (pin "32") (pinfunction "VDD_1_32") (pintype "passive"))
      (node (ref "U1") (pin "48") (pinfunction "VDD_2_48") (pintype "passive"))
      (node (ref "U1") (pin "64") (pinfunction "VDD_3_64") (pintype "passive"))
      (node (ref "U3") (pin "2") (pinfunction "OUT_2") (pintype "passive"))
      (node (ref "U3") (pin "4") (pinfunction "OUT_4") (pintype "passive"))
    )
    (net (code "70") (name "VCC5") (class "Default")
      (node (ref "B1") (pin "2") (pinfunction "+_2") (pintype "passive"))
      (node (ref "C10") (pin "2") (pinfunction "2_2") (pintype "passive"))
      (node (ref "C14") (pin "2") (pinfunction "2_2") (pintype "passive"))
      (node (ref "C8") (pin "2") (pintype "passive"))
      (node (ref "D1") (pin "2") (pinfunction "K_2") (pintype "passive"))
      (node (ref "H1") (pin "5") (pinfunction "+5V_5") (pintype "passive"))
      (node (ref "H2") (pin "1") (pinfunction "VCC_1") (pintype "passive"))
      (node (ref "H3") (pin "1") (pinfunction "VCC_1") (pintype "passive"))
      (node (ref "Header2") (pin "1") (pinfunction "VBUS_1") (pintype "passive"))
      (node (ref "Header4") (pin "9") (pinfunction "9_9") (pintype "passive"))
      (node (ref "Header5") (pin "9") (pinfunction "9_9") (pintype "passive"))
      (node (ref "Header7") (pin "9") (pinfunction "9_9") (pintype "passive"))
      (node (ref "P3") (pin "1") (pinfunction "1_1") (pintype "passive"))
      (node (ref "U2") (pin "16") (pinfunction "VCC_16") (pintype "passive"))
      (node (ref "U3") (pin "3") (pinfunction "IN_3") (pintype "passive"))
    )
    (net (code "71") (name "unconnected-(H1-EN-Pad6)") (class "Default")
      (node (ref "H1") (pin "6") (pinfunction "EN_6") (pintype "passive"))
    )
    (net (code "72") (name "unconnected-(H1-STATE-Pad1)") (class "Default")
      (node (ref "H1") (pin "1") (pinfunction "STATE_1") (pintype "passive"))
    )
    (net (code "73") (name "unconnected-(H2-NC-Pad3)") (class "Default")
      (node (ref "H2") (pin "3") (pinfunction "NC_3") (pintype "passive"))
    )
    (net (code "74") (name "unconnected-(Header1-Pad6)") (class "Default")
      (node (ref "Header1") (pin "6") (pinfunction "6_6") (pintype "passive"))
    )
    (net (code "75") (name "unconnected-(U1-PC12{slash}UART5_TX{slash}SDIO_CK-Pad53)") (class "Default")
      (node (ref "U1") (pin "53") (pinfunction "PC12/UART5_TX/SDIO_CK_53") (pintype "passive"))
    )
    (net (code "76") (name "unconnected-(U1-PC14{slash}OSC32_IN-Pad3)") (class "Default")
      (node (ref "U1") (pin "3") (pinfunction "PC14/OSC32_IN_3") (pintype "passive"))
    )
    (net (code "77") (name "unconnected-(U1-PC15{slash}OSC32_OUT-Pad4)") (class "Default")
      (node (ref "U1") (pin "4") (pinfunction "PC15/OSC32_OUT_4") (pintype "passive"))
    )
    (net (code "78") (name "unconnected-(U2-CTS-Pad9)") (class "Default")
      (node (ref "U2") (pin "9") (pinfunction "CTS_9") (pintype "passive"))
    )
    (net (code "79") (name "unconnected-(U2-DCD-Pad12)") (class "Default")
      (node (ref "U2") (pin "12") (pinfunction "DCD_12") (pintype "passive"))
    )
    (net (code "80") (name "unconnected-(U2-DSR-Pad10)") (class "Default")
      (node (ref "U2") (pin "10") (pinfunction "DSR_10") (pintype "passive"))
    )
    (net (code "81") (name "unconnected-(U2-DTR-Pad13)") (class "Default")
      (node (ref "U2") (pin "13") (pinfunction "DTR_13") (pintype "passive"))
    )
    (net (code "82") (name "unconnected-(U2-RI-Pad11)") (class "Default")
      (node (ref "U2") (pin "11") (pinfunction "RI_11") (pintype "passive"))
    )
    (net (code "83") (name "unconnected-(U2-RS232-Pad15)") (class "Default")
      (node (ref "U2") (pin "15") (pinfunction "RS232_15") (pintype "passive"))
    )
    (net (code "84") (name "unconnected-(U2-RTS-Pad14)") (class "Default")
      (node (ref "U2") (pin "14") (pinfunction "RTS_14") (pintype "passive"))
    )
  )
)
